# range_tag.net
KiCad netlist of a schematic drawn in EAGLE
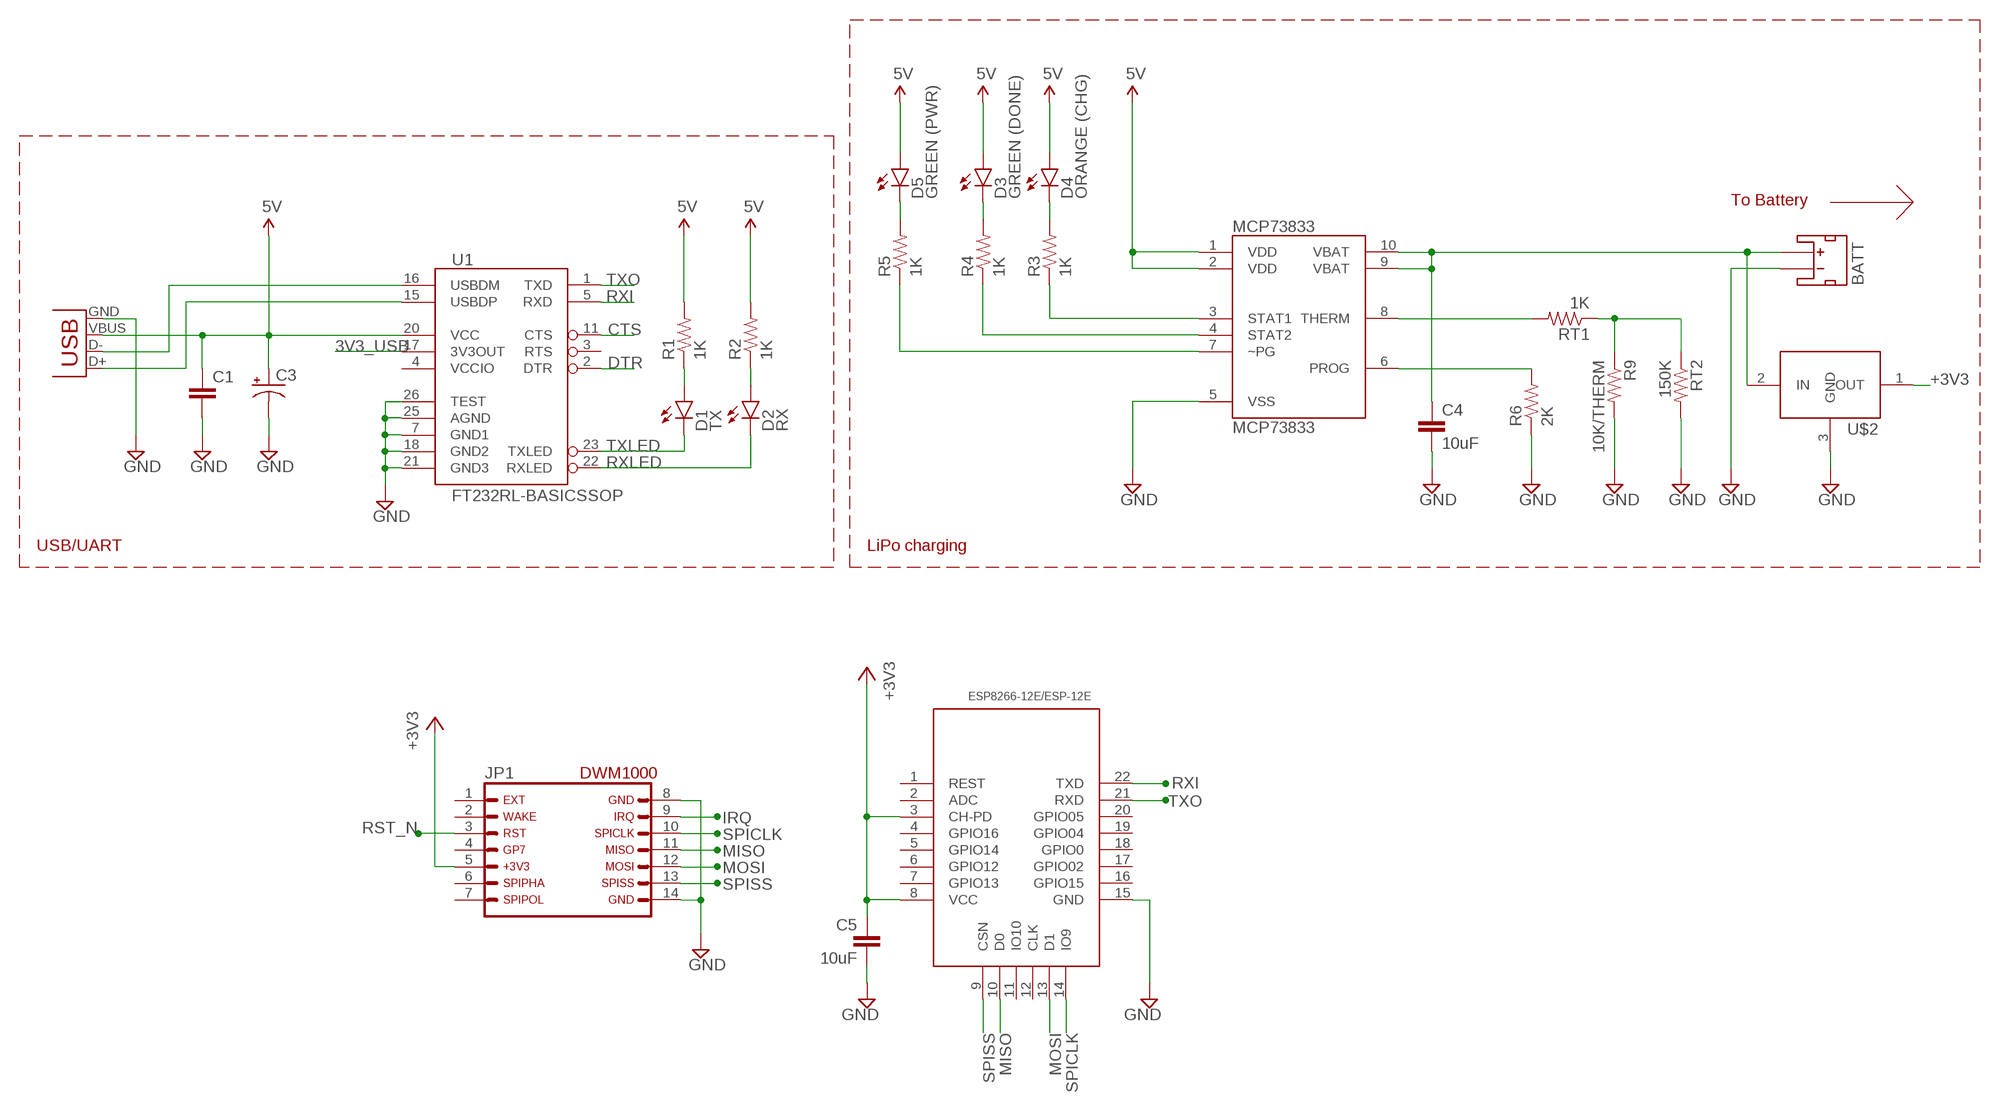
[diagram p0: schematic, sheet 1]

(export (version "E")
  (design (tool "Eeschema 10.0.6"))
  (components
    (comp (ref "BATT")
      (value "JST_2MM_MALE")
      (footprint "eagle-import:JST-2-SMD")
      (libsource (lib "eagle-import") (part "JST_2MM_MALE"))
    )
    (comp (ref "C1")
      (value "CAP0805")
      (footprint "eagle-import:0805")
      (libsource (lib "eagle-import") (part "CAP0805"))
    )
    (comp (ref "C3")
      (value "CAP_POL1206-KIT")
      (footprint "eagle-import:EIA3216-KIT")
      (libsource (lib "eagle-import") (part "CAP_POL1206-KIT"))
    )
    (comp (ref "C4")
      (value "10uF")
      (footprint "eagle-import:1206")
      (libsource (lib "eagle-import") (part "10UF-6.3V-20%(1206)"))
    )
    (comp (ref "C5")
      (value "10uF")
      (footprint "eagle-import:1206")
      (libsource (lib "eagle-import") (part "10UF-6.3V-20%(1206)"))
    )
    (comp (ref "D1")
      (value "TX")
      (footprint "eagle-import:LED-1206")
      (libsource (lib "eagle-import") (part "LED-GREENLARGE"))
    )
    (comp (ref "D2")
      (value "RX")
      (footprint "eagle-import:LED-1206")
      (libsource (lib "eagle-import") (part "LED-GREENLARGE"))
    )
    (comp (ref "D3")
      (value "GREEN (DONE)")
      (footprint "eagle-import:LED-1206")
      (libsource (lib "eagle-import") (part "LED-GREENLARGE"))
    )
    (comp (ref "D4")
      (value "ORANGE (CHG)")
      (footprint "eagle-import:LED-1206")
      (libsource (lib "eagle-import") (part "LED-GREENLARGE"))
    )
    (comp (ref "D5")
      (value "GREEN (PWR)")
      (footprint "eagle-import:LED-1206")
      (libsource (lib "eagle-import") (part "LED-GREENLARGE"))
    )
    (comp (ref "JP1")
      (value "DWM1000-DIPDWM1000-BREAKOUT")
      (footprint "eagle-import:2X07_HOLES_ONLY")
      (libsource (lib "eagle-import") (part "DWM1000-DIPDWM1000-BREAKOUT"))
    )
    (comp (ref "JP2")
      (value "USB-SMD-NS")
      (footprint "eagle-import:USB-MINIB-NOSTOP")
      (libsource (lib "eagle-import") (part "USB-SMD-NS"))
    )
    (comp (ref "MCP73833")
      (value "MCP73833")
      (footprint "eagle-import:MSOP-10")
      (libsource (lib "eagle-import") (part "MCP73833"))
    )
    (comp (ref "R1")
      (value "1K")
      (footprint "eagle-import:1206")
      (libsource (lib "eagle-import") (part "RESISTOR1206"))
    )
    (comp (ref "R2")
      (value "1K")
      (footprint "eagle-import:1206")
      (libsource (lib "eagle-import") (part "RESISTOR1206"))
    )
    (comp (ref "R3")
      (value "1K")
      (footprint "eagle-import:1206")
      (libsource (lib "eagle-import") (part "RESISTOR1206"))
    )
    (comp (ref "R4")
      (value "1K")
      (footprint "eagle-import:1206")
      (libsource (lib "eagle-import") (part "RESISTOR1206"))
    )
    (comp (ref "R5")
      (value "1K")
      (footprint "eagle-import:1206")
      (libsource (lib "eagle-import") (part "RESISTOR1206"))
    )
    (comp (ref "R6")
      (value "2K")
      (footprint "eagle-import:1206")
      (libsource (lib "eagle-import") (part "RESISTOR1206"))
    )
    (comp (ref "R9")
      (value "10K/THERM")
      (footprint "eagle-import:1206")
      (libsource (lib "eagle-import") (part "RESISTOR1206"))
    )
    (comp (ref "RT1")
      (value "1K")
      (footprint "eagle-import:1206")
      (libsource (lib "eagle-import") (part "RESISTOR1206"))
    )
    (comp (ref "RT2")
      (value "150K")
      (footprint "eagle-import:1206")
      (libsource (lib "eagle-import") (part "RESISTOR1206"))
    )
    (comp (ref "U$2")
      (value "LM3480IM4")
      (footprint "eagle-import:SOT23-3")
      (libsource (lib "eagle-import") (part "LM3480IM4"))
    )
    (comp (ref "U1")
      (value "FT232RL-BASICSSOP")
      (footprint "eagle-import:SSOP28DB")
      (libsource (lib "eagle-import") (part "FT232RL-BASICSSOP"))
    )
    (comp (ref "U3")
      (value "ESP8266-12E/ESP-12E")
      (footprint "eagle-import:LGA22-2.0-24X16MM")
      (libsource (lib "eagle-import") (part "MOUDLE-WIFI-ESP8266-12E/ESP-12E(22P-24X16MM)"))
    )
  )
  (nets
    (net (code "1") (name "+3V3") (class "Default")
      (node (ref "C5") (pin "1") (pinfunction "1_1") (pintype "passive"))
      (node (ref "JP1") (pin "5") (pinfunction "5_5") (pintype "passive"))
      (node (ref "U$2") (pin "1") (pinfunction "OUT_1") (pintype "bidirectional"))
      (node (ref "U3") (pin "3") (pinfunction "CH-PD_3") (pintype "bidirectional"))
      (node (ref "U3") (pin "8") (pinfunction "VCC_8") (pintype "bidirectional"))
    )
    (net (code "2") (name "/3V3_USB") (class "Default")
      (node (ref "U1") (pin "17") (pinfunction "3V3OUT_17") (pintype "output"))
    )
    (net (code "3") (name "/CTS") (class "Default")
      (node (ref "U1") (pin "11") (pinfunction "CTS_11") (pintype "bidirectional"))
    )
    (net (code "4") (name "/DTR") (class "Default")
      (node (ref "U1") (pin "2") (pinfunction "DTR_2") (pintype "bidirectional"))
    )
    (net (code "5") (name "/IRQ") (class "Default")
      (node (ref "JP1") (pin "9") (pinfunction "9_9") (pintype "passive"))
    )
    (net (code "6") (name "/MISO") (class "Default")
      (node (ref "JP1") (pin "11") (pinfunction "11_11") (pintype "passive"))
      (node (ref "U3") (pin "10") (pinfunction "D0_10") (pintype "bidirectional"))
    )
    (net (code "7") (name "/MOSI") (class "Default")
      (node (ref "JP1") (pin "12") (pinfunction "12_12") (pintype "passive"))
      (node (ref "U3") (pin "13") (pinfunction "D1_13") (pintype "bidirectional"))
    )
    (net (code "8") (name "/RST_N") (class "Default")
      (node (ref "JP1") (pin "3") (pinfunction "3_3") (pintype "passive"))
    )
    (net (code "9") (name "/RXI") (class "Default")
      (node (ref "U1") (pin "5") (pinfunction "RXD_5") (pintype "input"))
      (node (ref "U3") (pin "22") (pinfunction "TXD_22") (pintype "bidirectional"))
    )
    (net (code "10") (name "/RXLED") (class "Default")
      (node (ref "D2") (pin "C") (pinfunction "C_C") (pintype "passive"))
      (node (ref "U1") (pin "22") (pinfunction "RXLED_22") (pintype "bidirectional"))
    )
    (net (code "11") (name "/SPICLK") (class "Default")
      (node (ref "JP1") (pin "10") (pinfunction "10_10") (pintype "passive"))
      (node (ref "U3") (pin "14") (pinfunction "IO9_14") (pintype "bidirectional"))
    )
    (net (code "12") (name "/SPISS") (class "Default")
      (node (ref "JP1") (pin "13") (pinfunction "13_13") (pintype "passive"))
      (node (ref "U3") (pin "9") (pinfunction "CSN_9") (pintype "bidirectional"))
    )
    (net (code "13") (name "/TXLED") (class "Default")
      (node (ref "D1") (pin "C") (pinfunction "C_C") (pintype "passive"))
      (node (ref "U1") (pin "23") (pinfunction "TXLED_23") (pintype "bidirectional"))
    )
    (net (code "14") (name "/TXO") (class "Default")
      (node (ref "U1") (pin "1") (pinfunction "TXD_1") (pintype "output"))
      (node (ref "U3") (pin "21") (pinfunction "RXD_21") (pintype "bidirectional"))
    )
    (net (code "15") (name "/VCCIO") (class "Default")
      (node (ref "U1") (pin "4") (pinfunction "VCCIO_4") (pintype "power_in"))
    )
    (net (code "16") (name "5V") (class "Default")
      (node (ref "C1") (pin "1") (pinfunction "1_1") (pintype "passive"))
      (node (ref "C3") (pin "A") (pinfunction "+_A") (pintype "passive"))
      (node (ref "D3") (pin "A") (pinfunction "A_A") (pintype "passive"))
      (node (ref "D4") (pin "A") (pinfunction "A_A") (pintype "passive"))
      (node (ref "D5") (pin "A") (pinfunction "A_A") (pintype "passive"))
      (node (ref "JP2") (pin "VBUS") (pinfunction "VBUS_VBUS") (pintype "bidirectional"))
      (node (ref "MCP73833") (pin "1") (pinfunction "VDD_1") (pintype "bidirectional"))
      (node (ref "MCP73833") (pin "2") (pinfunction "VDD_2") (pintype "bidirectional"))
      (node (ref "R1") (pin "2") (pinfunction "2_2") (pintype "passive"))
      (node (ref "R2") (pin "2") (pinfunction "2_2") (pintype "passive"))
      (node (ref "U1") (pin "20") (pinfunction "VCC_20") (pintype "power_in"))
    )
    (net (code "17") (name "GND") (class "Default")
      (node (ref "BATT") (pin "1") (pinfunction "-_1") (pintype "bidirectional"))
      (node (ref "C1") (pin "2") (pinfunction "2_2") (pintype "passive"))
      (node (ref "C3") (pin "C") (pinfunction "-_C") (pintype "passive"))
      (node (ref "C4") (pin "2") (pinfunction "2_2") (pintype "passive"))
      (node (ref "C5") (pin "2") (pinfunction "2_2") (pintype "passive"))
      (node (ref "JP1") (pin "14") (pinfunction "14_14") (pintype "passive"))
      (node (ref "JP1") (pin "8") (pinfunction "8_8") (pintype "passive"))
      (node (ref "JP2") (pin "GND") (pinfunction "GND_GND") (pintype "bidirectional"))
      (node (ref "MCP73833") (pin "5") (pinfunction "VSS_5") (pintype "bidirectional"))
      (node (ref "R6") (pin "1") (pinfunction "1_1") (pintype "passive"))
      (node (ref "R9") (pin "2") (pinfunction "2_2") (pintype "passive"))
      (node (ref "RT2") (pin "2") (pinfunction "2_2") (pintype "passive"))
      (node (ref "U$2") (pin "3") (pinfunction "GND_3") (pintype "bidirectional"))
      (node (ref "U1") (pin "18") (pinfunction "GND2_18") (pintype "power_in"))
      (node (ref "U1") (pin "21") (pinfunction "GND3_21") (pintype "power_in"))
      (node (ref "U1") (pin "25") (pinfunction "AGND_25") (pintype "power_in"))
      (node (ref "U1") (pin "26") (pinfunction "TEST_26") (pintype "input"))
      (node (ref "U1") (pin "7") (pinfunction "GND1_7") (pintype "power_in"))
      (node (ref "U3") (pin "15") (pinfunction "GND_15") (pintype "bidirectional"))
    )
    (net (code "18") (name "Net-(BATT-+)") (class "Default")
      (node (ref "BATT") (pin "2") (pinfunction "+_2") (pintype "bidirectional"))
      (node (ref "C4") (pin "1") (pinfunction "1_1") (pintype "passive"))
      (node (ref "MCP73833") (pin "10") (pinfunction "VBAT_10") (pintype "bidirectional"))
      (node (ref "MCP73833") (pin "9") (pinfunction "VBAT_9") (pintype "bidirectional"))
      (node (ref "U$2") (pin "2") (pinfunction "IN_2") (pintype "bidirectional"))
    )
    (net (code "19") (name "Net-(D1-PadA)") (class "Default")
      (node (ref "D1") (pin "A") (pinfunction "A_A") (pintype "passive"))
      (node (ref "R1") (pin "1") (pinfunction "1_1") (pintype "passive"))
    )
    (net (code "20") (name "Net-(D2-PadA)") (class "Default")
      (node (ref "D2") (pin "A") (pinfunction "A_A") (pintype "passive"))
      (node (ref "R2") (pin "1") (pinfunction "1_1") (pintype "passive"))
    )
    (net (code "21") (name "Net-(D3-PadC)") (class "Default")
      (node (ref "D3") (pin "C") (pinfunction "C_C") (pintype "passive"))
      (node (ref "R4") (pin "2") (pinfunction "2_2") (pintype "passive"))
    )
    (net (code "22") (name "Net-(D4-PadC)") (class "Default")
      (node (ref "D4") (pin "C") (pinfunction "C_C") (pintype "passive"))
      (node (ref "R3") (pin "2") (pinfunction "2_2") (pintype "passive"))
    )
    (net (code "23") (name "Net-(D5-PadC)") (class "Default")
      (node (ref "D5") (pin "C") (pinfunction "C_C") (pintype "passive"))
      (node (ref "R5") (pin "2") (pinfunction "2_2") (pintype "passive"))
    )
    (net (code "24") (name "Net-(MCP73833-PROG)") (class "Default")
      (node (ref "MCP73833") (pin "6") (pinfunction "PROG_6") (pintype "bidirectional"))
      (node (ref "R6") (pin "2") (pinfunction "2_2") (pintype "passive"))
    )
    (net (code "25") (name "Net-(MCP73833-STAT1)") (class "Default")
      (node (ref "MCP73833") (pin "3") (pinfunction "STAT1_3") (pintype "bidirectional"))
      (node (ref "R3") (pin "1") (pinfunction "1_1") (pintype "passive"))
    )
    (net (code "26") (name "Net-(MCP73833-STAT2)") (class "Default")
      (node (ref "MCP73833") (pin "4") (pinfunction "STAT2_4") (pintype "bidirectional"))
      (node (ref "R4") (pin "1") (pinfunction "1_1") (pintype "passive"))
    )
    (net (code "27") (name "Net-(MCP73833-THERM)") (class "Default")
      (node (ref "MCP73833") (pin "8") (pinfunction "THERM_8") (pintype "bidirectional"))
      (node (ref "RT1") (pin "2") (pinfunction "2_2") (pintype "passive"))
    )
    (net (code "28") (name "Net-(MCP73833-~{PG})") (class "Default")
      (node (ref "MCP73833") (pin "7") (pinfunction "~{PG}_7") (pintype "bidirectional"))
      (node (ref "R5") (pin "1") (pinfunction "1_1") (pintype "passive"))
    )
    (net (code "29") (name "Net-(R9-Pad1)") (class "Default")
      (node (ref "R9") (pin "1") (pinfunction "1_1") (pintype "passive"))
      (node (ref "RT1") (pin "1") (pinfunction "1_1") (pintype "passive"))
      (node (ref "RT2") (pin "1") (pinfunction "1_1") (pintype "passive"))
    )
    (net (code "30") (name "Net-(U1-USBDM)") (class "Default")
      (node (ref "JP2") (pin "D-") (pinfunction "D-_D-") (pintype "bidirectional"))
      (node (ref "U1") (pin "16") (pinfunction "USBDM_16") (pintype "bidirectional"))
    )
    (net (code "31") (name "Net-(U1-USBDP)") (class "Default")
      (node (ref "JP2") (pin "D+") (pinfunction "D+_D+") (pintype "bidirectional"))
      (node (ref "U1") (pin "15") (pinfunction "USBDP_15") (pintype "bidirectional"))
    )
    (net (code "32") (name "unconnected-(BATT-PAD1-PadNC1)") (class "Default")
      (node (ref "BATT") (pin "NC1") (pinfunction "PAD1_NC1") (pintype "bidirectional"))
    )
    (net (code "33") (name "unconnected-(BATT-PAD2-PadNC2)") (class "Default")
      (node (ref "BATT") (pin "NC2") (pinfunction "PAD2_NC2") (pintype "bidirectional"))
    )
    (net (code "34") (name "unconnected-(JP1-Pad1)") (class "Default")
      (node (ref "JP1") (pin "1") (pinfunction "1_1") (pintype "passive"))
    )
    (net (code "35") (name "unconnected-(JP1-Pad2)") (class "Default")
      (node (ref "JP1") (pin "2") (pinfunction "2_2") (pintype "passive"))
    )
    (net (code "36") (name "unconnected-(JP1-Pad4)") (class "Default")
      (node (ref "JP1") (pin "4") (pinfunction "4_4") (pintype "passive"))
    )
    (net (code "37") (name "unconnected-(JP1-Pad6)") (class "Default")
      (node (ref "JP1") (pin "6") (pinfunction "6_6") (pintype "passive"))
    )
    (net (code "38") (name "unconnected-(JP1-Pad7)") (class "Default")
      (node (ref "JP1") (pin "7") (pinfunction "7_7") (pintype "passive"))
    )
    (net (code "39") (name "unconnected-(U1-RTS-Pad3)") (class "Default")
      (node (ref "U1") (pin "3") (pinfunction "RTS_3") (pintype "bidirectional"))
    )
    (net (code "40") (name "unconnected-(U3-ADC-Pad2)") (class "Default")
      (node (ref "U3") (pin "2") (pinfunction "ADC_2") (pintype "bidirectional"))
    )
    (net (code "41") (name "unconnected-(U3-CLK-Pad12)") (class "Default")
      (node (ref "U3") (pin "12") (pinfunction "CLK_12") (pintype "bidirectional"))
    )
    (net (code "42") (name "unconnected-(U3-GPIO0-Pad18)") (class "Default")
      (node (ref "U3") (pin "18") (pinfunction "GPIO0_18") (pintype "bidirectional"))
    )
    (net (code "43") (name "unconnected-(U3-GPIO02-Pad17)") (class "Default")
      (node (ref "U3") (pin "17") (pinfunction "GPIO02_17") (pintype "bidirectional"))
    )
    (net (code "44") (name "unconnected-(U3-GPIO04-Pad19)") (class "Default")
      (node (ref "U3") (pin "19") (pinfunction "GPIO04_19") (pintype "bidirectional"))
    )
    (net (code "45") (name "unconnected-(U3-GPIO05-Pad20)") (class "Default")
      (node (ref "U3") (pin "20") (pinfunction "GPIO05_20") (pintype "bidirectional"))
    )
    (net (code "46") (name "unconnected-(U3-GPIO12-Pad6)") (class "Default")
      (node (ref "U3") (pin "6") (pinfunction "GPIO12_6") (pintype "bidirectional"))
    )
    (net (code "47") (name "unconnected-(U3-GPIO13-Pad7)") (class "Default")
      (node (ref "U3") (pin "7") (pinfunction "GPIO13_7") (pintype "bidirectional"))
    )
    (net (code "48") (name "unconnected-(U3-GPIO14-Pad5)") (class "Default")
      (node (ref "U3") (pin "5") (pinfunction "GPIO14_5") (pintype "bidirectional"))
    )
    (net (code "49") (name "unconnected-(U3-GPIO15-Pad16)") (class "Default")
      (node (ref "U3") (pin "16") (pinfunction "GPIO15_16") (pintype "bidirectional"))
    )
    (net (code "50") (name "unconnected-(U3-GPIO16-Pad4)") (class "Default")
      (node (ref "U3") (pin "4") (pinfunction "GPIO16_4") (pintype "bidirectional"))
    )
    (net (code "51") (name "unconnected-(U3-IO10-Pad11)") (class "Default")
      (node (ref "U3") (pin "11") (pinfunction "IO10_11") (pintype "bidirectional"))
    )
    (net (code "52") (name "unconnected-(U3-REST-Pad1)") (class "Default")
      (node (ref "U3") (pin "1") (pinfunction "REST_1") (pintype "bidirectional"))
    )
  )
)
